# NRF52840-Beacon-V1-1.net
KiCad netlist of a schematic drawn in Altium Designer
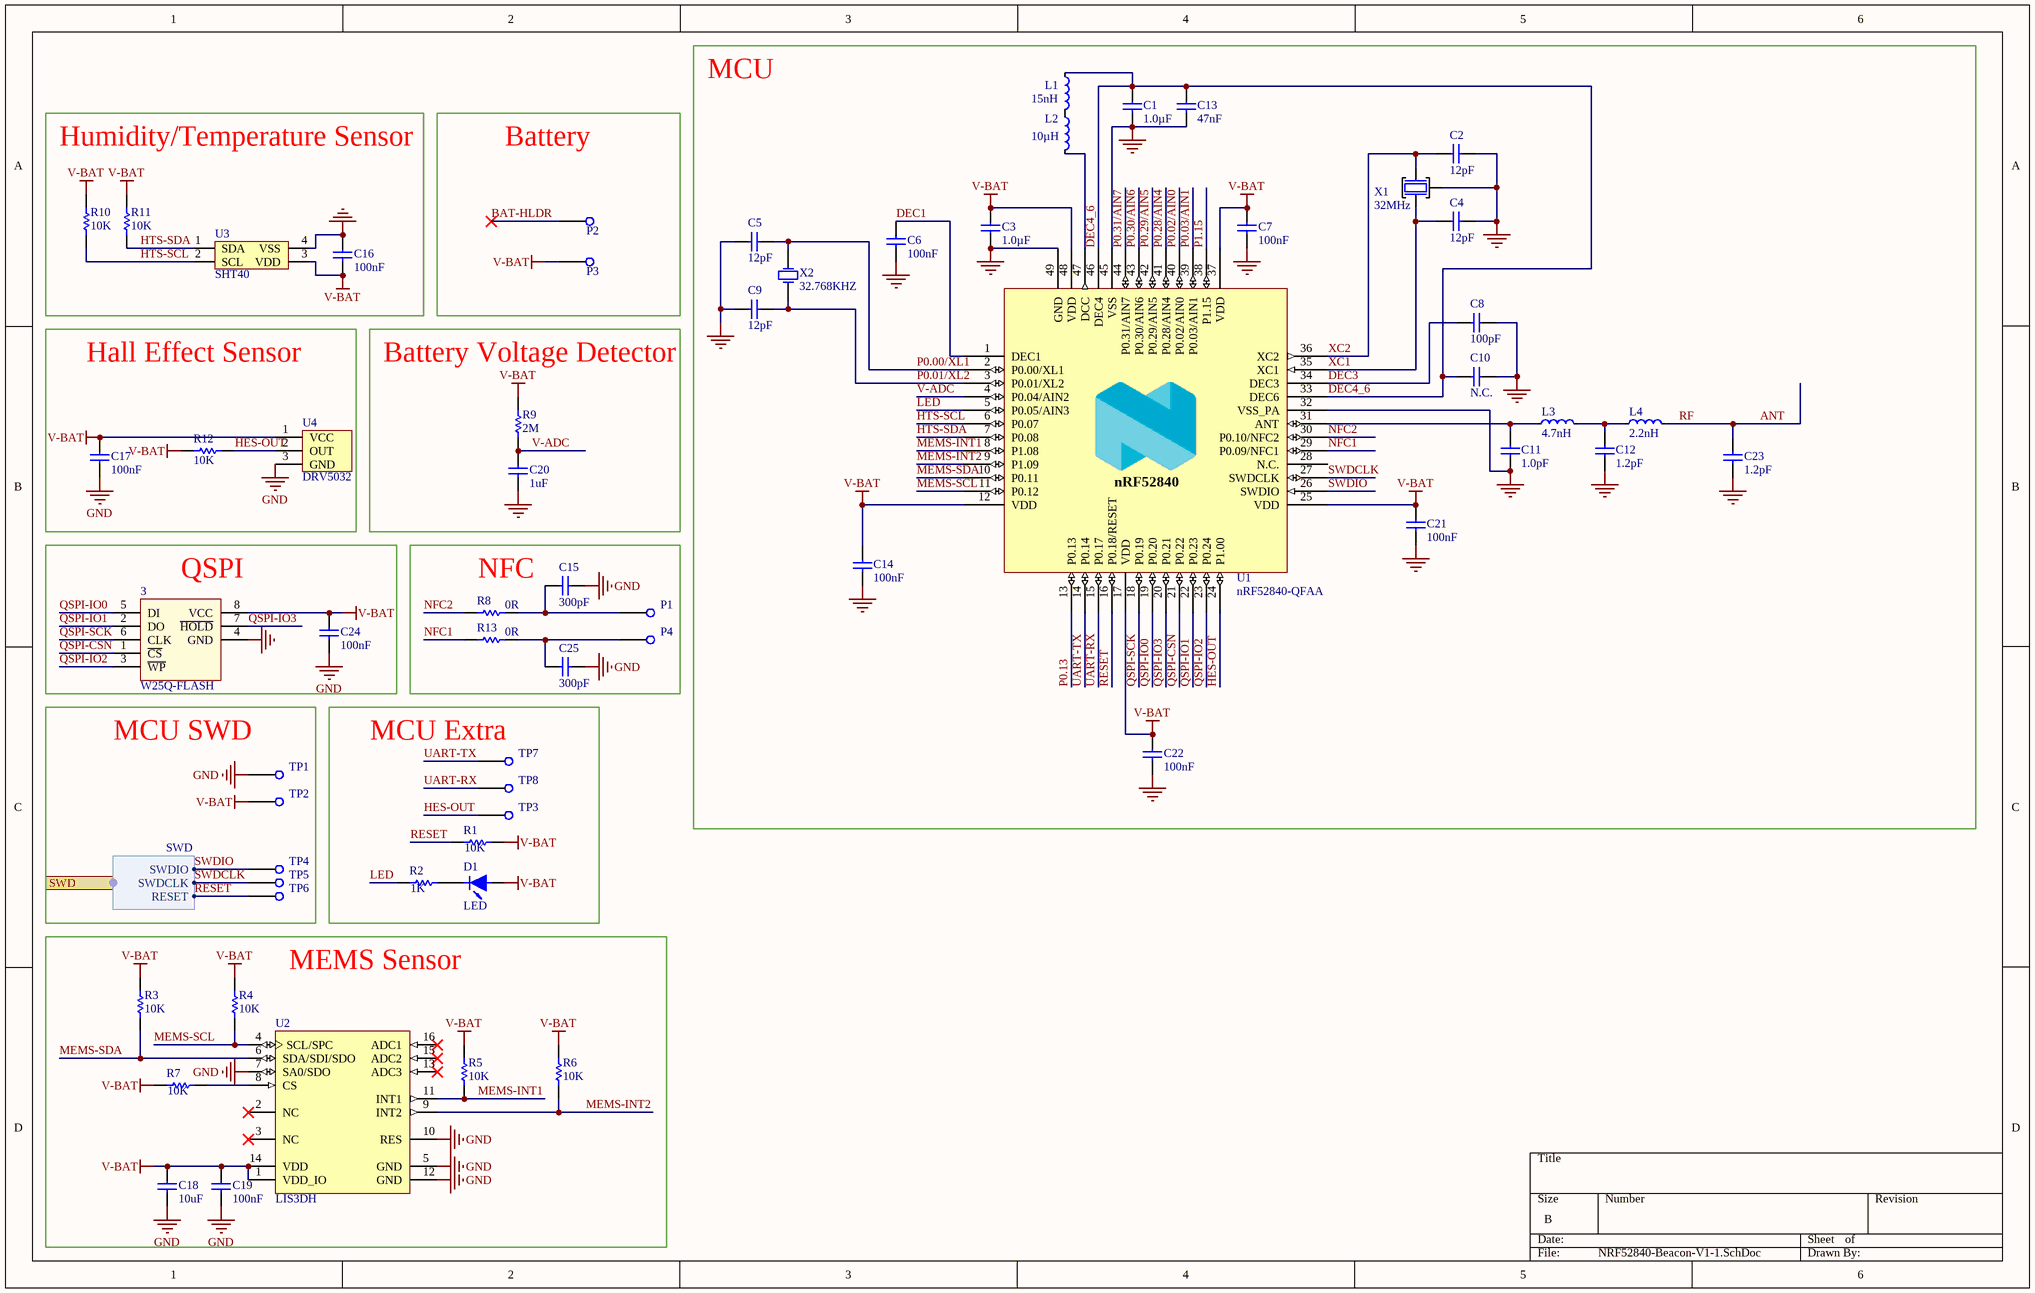
[diagram p0: NRF52840-Beacon-V1-1.SchDoc]

(export (version "E")
  (design (tool "Eeschema 10.0.6"))
  (components
    (comp (ref "3")
      (value "W25Q-FLASH")
      (footprint "SO8W_M")
      (libsource (lib "My Devices") (part "W25Q-FLASH"))
    )
    (comp (ref "C1")
      (value "1.0µF")
      (footprint "CAPC1608N")
      (description "Capacitor, X5R, ±10%")
      (fields (field (name "PART NUMBER") "C0402-1µ0"))
      (libsource (lib "AltiumLib") (part "CAP"))
    )
    (comp (ref "C2")
      (value "12pF")
      (footprint "CAPC1608N")
      (description "Capacitor, NP0, ±2%")
      (fields (field (name "PART NUMBER") "C0201-12p"))
      (libsource (lib "AltiumLib") (part "CAP"))
    )
    (comp (ref "C3")
      (value "1.0µF")
      (footprint "CAPC1608N")
      (description "Capacitor, X5R, ±10%")
      (fields (field (name "PART NUMBER") "C0402-1µ0"))
      (libsource (lib "AltiumLib") (part "CAP"))
    )
    (comp (ref "C4")
      (value "12pF")
      (footprint "CAPC1608N")
      (description "Capacitor, NP0, ±2%")
      (fields (field (name "PART NUMBER") "C0201-12p"))
      (libsource (lib "AltiumLib") (part "CAP"))
    )
    (comp (ref "C5")
      (value "12pF")
      (footprint "CAPC1608N")
      (description "Capacitor, NP0, ±2%")
      (fields (field (name "PART NUMBER") "C0201-12p"))
      (libsource (lib "AltiumLib") (part "CAP"))
    )
    (comp (ref "C6")
      (value "100nF")
      (footprint "CAPC1608N")
      (description "Capacitor, X5R, ±10%")
      (fields (field (name "PART NUMBER") "C0201-100n"))
      (libsource (lib "AltiumLib") (part "CAP"))
    )
    (comp (ref "C7")
      (value "100nF")
      (footprint "CAPC1608N")
      (description "Capacitor, X5R, ±10%")
      (fields (field (name "PART NUMBER") "C0201-100n"))
      (libsource (lib "AltiumLib") (part "CAP"))
    )
    (comp (ref "C8")
      (value "100pF")
      (footprint "CAPC1608N")
      (description "Capacitor, NP0, ±5%")
      (fields (field (name "PART NUMBER") "C0201-100p"))
      (libsource (lib "AltiumLib") (part "CAP"))
    )
    (comp (ref "C9")
      (value "12pF")
      (footprint "CAPC1608N")
      (description "Capacitor, NP0, ±2%")
      (fields (field (name "PART NUMBER") "C0201-12p"))
      (libsource (lib "AltiumLib") (part "CAP"))
    )
    (comp (ref "C10")
      (value "N.C.")
      (footprint "CAPC1608N")
      (description "Not mounted")
      (fields (field (name "PART NUMBER") "C0201-N.C."))
      (libsource (lib "AltiumLib") (part "CAP"))
    )
    (comp (ref "C11")
      (value "1.0pF")
      (footprint "CAPC1608N")
      (description "Capacitor, NP0, ±10%")
      (fields (field (name "PART NUMBER") "C0201-1.0p"))
      (libsource (lib "AltiumLib") (part "CAP"))
    )
    (comp (ref "C12")
      (value "1.2pF")
      (footprint "CAPC1608N")
      (description "Capacitor, NP0, ±10%")
      (fields (field (name "PART NUMBER") "C0201-1.2p"))
      (libsource (lib "AltiumLib") (part "CAP"))
    )
    (comp (ref "C13")
      (value "47nF")
      (footprint "CAPC1608N")
      (description "Capacitor, X5R, ±10%")
      (fields (field (name "PART NUMBER") "C0201-47n"))
      (libsource (lib "AltiumLib") (part "CAP"))
    )
    (comp (ref "C14")
      (value "100nF")
      (footprint "CAPC1608N")
      (description "Capacitor, X5R, ±10%")
      (fields (field (name "PART NUMBER") "C0201-100n"))
      (libsource (lib "AltiumLib") (part "CAP"))
    )
    (comp (ref "C15")
      (value "300pF")
      (footprint "CAPC1608N")
      (description "Capacitor, NP0, ±2%")
      (fields (field (name "PART NUMBER") "C0201-12p"))
      (libsource (lib "AltiumLib") (part "CAP"))
    )
    (comp (ref "C16")
      (value "100nF")
      (footprint "CAPC1608N")
      (description "Capacitor, NP0, ±2%")
      (fields (field (name "PART NUMBER") "C0201-12p"))
      (libsource (lib "AltiumLib") (part "CAP"))
    )
    (comp (ref "C17")
      (value "100nF")
      (footprint "CAPC1608N")
      (description "Capacitor, NP0, ±2%")
      (fields (field (name "PART NUMBER") "C0201-12p"))
      (libsource (lib "AltiumLib") (part "CAP"))
    )
    (comp (ref "C18")
      (value "10uF")
      (footprint "CAPC1608N")
      (description "Capacitor, NP0, ±2%")
      (fields (field (name "PART NUMBER") "C0201-12p"))
      (libsource (lib "AltiumLib") (part "CAP"))
    )
    (comp (ref "C19")
      (value "100nF")
      (footprint "CAPC1608N")
      (description "Capacitor, NP0, ±2%")
      (fields (field (name "PART NUMBER") "C0201-12p"))
      (libsource (lib "AltiumLib") (part "CAP"))
    )
    (comp (ref "C20")
      (value "1uF")
      (footprint "CAPC1608N")
      (description "Capacitor, NP0, ±2%")
      (fields (field (name "PART NUMBER") "C0201-12p"))
      (libsource (lib "AltiumLib") (part "CAP"))
    )
    (comp (ref "C21")
      (value "100nF")
      (footprint "CAPC1608N")
      (description "Capacitor, X5R, ±10%")
      (fields (field (name "PART NUMBER") "C0201-100n"))
      (libsource (lib "AltiumLib") (part "CAP"))
    )
    (comp (ref "C22")
      (value "100nF")
      (footprint "CAPC1608N")
      (description "Capacitor, X5R, ±10%")
      (fields (field (name "PART NUMBER") "C0201-100n"))
      (libsource (lib "AltiumLib") (part "CAP"))
    )
    (comp (ref "C23")
      (value "1.2pF")
      (footprint "CAPC1608N")
      (description "Capacitor, NP0, ±10%")
      (fields (field (name "PART NUMBER") "C0201-1.2p"))
      (libsource (lib "AltiumLib") (part "CAP"))
    )
    (comp (ref "C24")
      (value "100nF")
      (footprint "CAPC1608N")
      (description "Capacitor, NP0, ±2%")
      (fields (field (name "PART NUMBER") "C0201-12p"))
      (libsource (lib "AltiumLib") (part "CAP"))
    )
    (comp (ref "C25")
      (value "300pF")
      (footprint "CAPC1608N")
      (description "Capacitor, NP0, ±2%")
      (fields (field (name "PART NUMBER") "C0201-12p"))
      (libsource (lib "AltiumLib") (part "CAP"))
    )
    (comp (ref "D1")
      (value "LED")
      (footprint "LED_0603")
      (fields (field (name "PUBLISHER") "Altium Limited"))
      (libsource (lib "My Devices") (part "LED"))
    )
    (comp (ref "L1")
      (value "15nH")
      (footprint "INDC1608N")
      (description "High frequency chip inductor ±10%")
      (fields (field (name "PART NUMBER") "L0402-15n"))
      (libsource (lib "AltiumLib") (part "IND"))
    )
    (comp (ref "L2")
      (value "10µH")
      (footprint "INDC1608N")
      (description "Chip inductor, IDC,min = 50 mA, ±20%")
      (fields (field (name "PART NUMBER") "L0603-10µ-TDK"))
      (libsource (lib "AltiumLib") (part "IND"))
    )
    (comp (ref "L3")
      (value "4.7nH")
      (footprint "INDC1608N")
      (description "High frequency chip inductor ±5%")
      (fields (field (name "PART NUMBER") "L0201-4n7"))
      (libsource (lib "AltiumLib") (part "IND"))
    )
    (comp (ref "L4")
      (value "2.2nH")
      (footprint "INDC1608N")
      (description "High frequency chip inductor ±5%")
      (fields (field (name "PART NUMBER") "L0201-2n2"))
      (libsource (lib "AltiumLib") (part "IND"))
    )
    (comp (ref "P1") (value "PIN") (footprint "PIN") (libsource (lib "My Connectors") (part "PIN")))
    (comp (ref "P2") (value "PIN") (footprint "PIN") (libsource (lib "My Connectors") (part "PIN")))
    (comp (ref "P3") (value "PIN") (footprint "PIN") (libsource (lib "My Connectors") (part "PIN")))
    (comp (ref "P4") (value "PIN") (footprint "PIN") (libsource (lib "My Connectors") (part "PIN")))
    (comp (ref "R1") (value "10K") (footprint "RESC1608N") (libsource (lib "My Devices") (part "Resistor")))
    (comp (ref "R2") (value "1K") (footprint "RESC1608N") (libsource (lib "My Devices") (part "Resistor")))
    (comp (ref "R3") (value "10K") (footprint "RESC1608N") (libsource (lib "My Devices") (part "Resistor")))
    (comp (ref "R4") (value "10K") (footprint "RESC1608N") (libsource (lib "My Devices") (part "Resistor")))
    (comp (ref "R5") (value "10K") (footprint "RESC1608N") (libsource (lib "My Devices") (part "Resistor")))
    (comp (ref "R6") (value "10K") (footprint "RESC1608N") (libsource (lib "My Devices") (part "Resistor")))
    (comp (ref "R7") (value "10K") (footprint "RESC1608N") (libsource (lib "My Devices") (part "Resistor")))
    (comp (ref "R8") (value "0R") (footprint "RESC1608N") (libsource (lib "My Devices") (part "Resistor")))
    (comp (ref "R9") (value "2M") (footprint "RESC1608N") (libsource (lib "My Devices") (part "Resistor")))
    (comp (ref "R10") (value "10K") (footprint "RESC1608N") (libsource (lib "My Devices") (part "Resistor")))
    (comp (ref "R11") (value "10K") (footprint "RESC1608N") (libsource (lib "My Devices") (part "Resistor")))
    (comp (ref "R12") (value "10K") (footprint "RESC1608N") (libsource (lib "My Devices") (part "Resistor")))
    (comp (ref "R13") (value "0R") (footprint "RESC1608N") (libsource (lib "My Devices") (part "Resistor")))
    (comp (ref "TP1") (value "PIN") (footprint "PIN") (libsource (lib "My Connectors") (part "PIN")))
    (comp (ref "TP2") (value "PIN") (footprint "PIN") (libsource (lib "My Connectors") (part "PIN")))
    (comp (ref "TP3") (value "PIN") (footprint "PIN") (libsource (lib "My Connectors") (part "PIN")))
    (comp (ref "TP4") (value "PIN") (footprint "PIN") (libsource (lib "My Connectors") (part "PIN")))
    (comp (ref "TP5") (value "PIN") (footprint "PIN") (libsource (lib "My Connectors") (part "PIN")))
    (comp (ref "TP6") (value "PIN") (footprint "PIN") (libsource (lib "My Connectors") (part "PIN")))
    (comp (ref "TP7") (value "PIN") (footprint "PIN") (libsource (lib "My Connectors") (part "PIN")))
    (comp (ref "TP8") (value "PIN") (footprint "PIN") (libsource (lib "My Connectors") (part "PIN")))
    (comp (ref "U1")
      (value "nRF52840-QFAA")
      (footprint "QFN40P600X600X90-48N")
      (description "Multi-protocol Bluetooth Low Energy, IEEE 802.15.4, ANT and 2.4GHz proprietary system-on-chip")
      (libsource (lib "AltiumLib") (part "nRF52840_QFAA"))
    )
    (comp (ref "U2")
      (value "LIS3DH")
      (footprint "LGA-16")
      (fields (field (name "MANUFACTURER") "STMicroelectronics"))
      (libsource (lib "My Devices") (part "LIS3DH"))
    )
    (comp (ref "U3")
      (value "SHT40")
      (footprint "SHT40")
      (description "High-Accuracy, Ultra-Low-Power, 16-bit, Relative Humidity and Temperature Sensor")
      (libsource (lib "My Devices") (part "SHT40"))
    )
    (comp (ref "U4")
      (value "DRV5032")
      (footprint "SOT-23")
      (description "ultra-low-power digital-switch Hall effect sensor")
      (libsource (lib "My Devices") (part "Hall_Effect_Sensor_Switch"))
    )
    (comp (ref "X1")
      (value "32MHz")
      (footprint "CRYSTAL_2016_NT")
      (description "XTAL SMD 2016, 32MHz, Cl=8pF, Total Tol: ±30ppm")
      (fields (field (name "PART NUMBER") "XTAL_SMD2016_32MHz_8pF_General_NT"))
      (libsource (lib "AltiumLib") (part "XTAL_4-pin_NT"))
    )
    (comp (ref "X2")
      (value "32.768KHZ")
      (footprint "CRYSTAL_3215")
      (libsource (lib "My Devices") (part "Crystal_Oscillator_2PIN"))
    )
  )
  (nets
    (net (code "2") (name "/ANT") (class "Default")
      (node (ref "C23") (pin "1") (pinfunction "1_1") (pintype "passive"))
      (node (ref "L4") (pin "2") (pinfunction "2_2") (pintype "passive"))
    )
    (net (code "3") (name "/BAT-HLDR") (class "Default")
      (node (ref "P2") (pin "1") (pinfunction "PIN_1") (pintype "passive+no_connect"))
    )
    (net (code "4") (name "/DEC1") (class "Default")
      (node (ref "C6") (pin "1") (pinfunction "1_1") (pintype "passive"))
      (node (ref "U1") (pin "1") (pinfunction "DEC1_1") (pintype "power_in"))
    )
    (net (code "5") (name "/DEC3") (class "Default")
      (node (ref "C8") (pin "1") (pinfunction "1_1") (pintype "passive"))
      (node (ref "U1") (pin "34") (pinfunction "DEC3_34") (pintype "power_in"))
    )
    (net (code "6") (name "/DEC4_6") (class "Default")
      (node (ref "C1") (pin "2") (pinfunction "2_2") (pintype "passive"))
      (node (ref "C10") (pin "2") (pinfunction "2_2") (pintype "passive"))
      (node (ref "C13") (pin "1") (pinfunction "1_1") (pintype "passive"))
      (node (ref "L1") (pin "1") (pinfunction "1_1") (pintype "passive"))
      (node (ref "U1") (pin "33") (pinfunction "DEC6_33") (pintype "power_in"))
      (node (ref "U1") (pin "46") (pinfunction "DEC4_46") (pintype "power_in"))
    )
    (net (code "7") (name "/HES-OUT") (class "Default")
      (node (ref "R12") (pin "2") (pinfunction "2_2") (pintype "passive"))
      (node (ref "TP3") (pin "1") (pinfunction "PIN_1") (pintype "passive"))
      (node (ref "U1") (pin "24") (pinfunction "P1.00_24") (pintype "bidirectional"))
      (node (ref "U4") (pin "2") (pinfunction "OUT_2") (pintype "passive"))
    )
    (net (code "8") (name "/HTS-SCL") (class "Default")
      (node (ref "R10") (pin "2") (pinfunction "2_2") (pintype "passive"))
      (node (ref "U1") (pin "6") (pinfunction "P0.07_6") (pintype "bidirectional"))
      (node (ref "U3") (pin "2") (pinfunction "SCL_2") (pintype "passive"))
    )
    (net (code "9") (name "/HTS-SDA") (class "Default")
      (node (ref "R11") (pin "2") (pinfunction "2_2") (pintype "passive"))
      (node (ref "U1") (pin "7") (pinfunction "P0.08_7") (pintype "bidirectional"))
      (node (ref "U3") (pin "1") (pinfunction "SDA_1") (pintype "passive"))
    )
    (net (code "10") (name "/LED") (class "Default")
      (node (ref "R2") (pin "1") (pinfunction "1_1") (pintype "passive"))
      (node (ref "U1") (pin "5") (pinfunction "P0.05/AIN3_5") (pintype "bidirectional"))
    )
    (net (code "11") (name "/MEMS-INT1") (class "Default")
      (node (ref "R5") (pin "2") (pinfunction "2_2") (pintype "passive"))
      (node (ref "U1") (pin "8") (pinfunction "P1.08_8") (pintype "bidirectional"))
      (node (ref "U2") (pin "11") (pinfunction "INT1_11") (pintype "output"))
    )
    (net (code "12") (name "/MEMS-INT2") (class "Default")
      (node (ref "R6") (pin "2") (pinfunction "2_2") (pintype "passive"))
      (node (ref "U1") (pin "9") (pinfunction "P1.09_9") (pintype "bidirectional"))
      (node (ref "U2") (pin "9") (pinfunction "INT2_9") (pintype "output"))
    )
    (net (code "13") (name "/MEMS-SCL") (class "Default")
      (node (ref "R4") (pin "2") (pinfunction "2_2") (pintype "passive"))
      (node (ref "U1") (pin "11") (pinfunction "P0.12_11") (pintype "bidirectional"))
      (node (ref "U2") (pin "4") (pinfunction "SCL/SPC_4") (pintype "bidirectional"))
    )
    (net (code "14") (name "/MEMS-SDA") (class "Default")
      (node (ref "R3") (pin "2") (pinfunction "2_2") (pintype "passive"))
      (node (ref "U1") (pin "10") (pinfunction "P0.11_10") (pintype "bidirectional"))
      (node (ref "U2") (pin "6") (pinfunction "SDA/SDI/SDO_6") (pintype "bidirectional"))
    )
    (net (code "15") (name "/NFC1") (class "Default")
      (node (ref "R13") (pin "2") (pinfunction "2_2") (pintype "passive"))
      (node (ref "U1") (pin "29") (pinfunction "P0.09/NFC1_29") (pintype "bidirectional"))
    )
    (net (code "16") (name "/NFC2") (class "Default")
      (node (ref "R8") (pin "2") (pinfunction "2_2") (pintype "passive"))
      (node (ref "U1") (pin "30") (pinfunction "P0.10/NFC2_30") (pintype "bidirectional"))
    )
    (net (code "17") (name "/P0.00{slash}XL1") (class "Default")
      (node (ref "C5") (pin "1") (pinfunction "1_1") (pintype "passive"))
      (node (ref "U1") (pin "2") (pinfunction "P0.00/XL1_2") (pintype "bidirectional"))
      (node (ref "X2") (pin "2") (pinfunction "OSC2_2") (pintype "passive"))
    )
    (net (code "18") (name "/P0.01{slash}XL2") (class "Default")
      (node (ref "C9") (pin "1") (pinfunction "1_1") (pintype "passive"))
      (node (ref "U1") (pin "3") (pinfunction "P0.01/XL2_3") (pintype "bidirectional"))
      (node (ref "X2") (pin "1") (pinfunction "OSC1_1") (pintype "passive"))
    )
    (net (code "19") (name "/P0.02{slash}AIN0") (class "Default")
      (node (ref "U1") (pin "40") (pinfunction "P0.02/AIN0_40") (pintype "bidirectional"))
    )
    (net (code "20") (name "/P0.03{slash}AIN1") (class "Default")
      (node (ref "U1") (pin "39") (pinfunction "P0.03/AIN1_39") (pintype "bidirectional"))
    )
    (net (code "21") (name "/P0.13") (class "Default")
      (node (ref "U1") (pin "13") (pinfunction "P0.13_13") (pintype "bidirectional"))
    )
    (net (code "22") (name "/P0.28{slash}AIN4") (class "Default")
      (node (ref "U1") (pin "41") (pinfunction "P0.28/AIN4_41") (pintype "bidirectional"))
    )
    (net (code "23") (name "/P0.29{slash}AIN5") (class "Default")
      (node (ref "U1") (pin "42") (pinfunction "P0.29/AIN5_42") (pintype "bidirectional"))
    )
    (net (code "24") (name "/P0.30{slash}AIN6") (class "Default")
      (node (ref "U1") (pin "43") (pinfunction "P0.30/AIN6_43") (pintype "bidirectional"))
    )
    (net (code "25") (name "/P0.31{slash}AIN7") (class "Default")
      (node (ref "U1") (pin "44") (pinfunction "P0.31/AIN7_44") (pintype "bidirectional"))
    )
    (net (code "26") (name "/P1.15") (class "Default")
      (node (ref "U1") (pin "38") (pinfunction "P1.15_38") (pintype "bidirectional"))
    )
    (net (code "27") (name "/QSPI-CSN") (class "Default")
      (node (ref "3") (pin "1") (pinfunction "~{CS}_1") (pintype "passive"))
      (node (ref "U1") (pin "21") (pinfunction "P0.22_21") (pintype "bidirectional"))
    )
    (net (code "28") (name "/QSPI-IO0") (class "Default")
      (node (ref "3") (pin "5") (pinfunction "DI_5") (pintype "passive"))
      (node (ref "U1") (pin "19") (pinfunction "P0.20_19") (pintype "bidirectional"))
    )
    (net (code "29") (name "/QSPI-IO1") (class "Default")
      (node (ref "3") (pin "2") (pinfunction "DO_2") (pintype "passive"))
      (node (ref "U1") (pin "22") (pinfunction "P0.23_22") (pintype "bidirectional"))
    )
    (net (code "30") (name "/QSPI-IO2") (class "Default")
      (node (ref "3") (pin "3") (pinfunction "~{WP}_3") (pintype "passive"))
      (node (ref "U1") (pin "23") (pinfunction "P0.24_23") (pintype "bidirectional"))
    )
    (net (code "31") (name "/QSPI-IO3") (class "Default")
      (node (ref "3") (pin "7") (pinfunction "~{HOLD}_7") (pintype "passive"))
      (node (ref "U1") (pin "20") (pinfunction "P0.21_20") (pintype "bidirectional"))
    )
    (net (code "32") (name "/QSPI-SCK") (class "Default")
      (node (ref "3") (pin "6") (pinfunction "CLK_6") (pintype "passive"))
      (node (ref "U1") (pin "18") (pinfunction "P0.19_18") (pintype "bidirectional"))
    )
    (net (code "33") (name "/RESET") (class "Default")
      (node (ref "R1") (pin "1") (pinfunction "1_1") (pintype "passive"))
      (node (ref "TP6") (pin "1") (pinfunction "PIN_1") (pintype "passive"))
      (node (ref "U1") (pin "16") (pinfunction "P0.18/RESET_16") (pintype "bidirectional"))
    )
    (net (code "34") (name "/SWDCLK") (class "Default")
      (node (ref "TP5") (pin "1") (pinfunction "PIN_1") (pintype "passive"))
      (node (ref "U1") (pin "27") (pinfunction "SWDCLK_27") (pintype "bidirectional"))
    )
    (net (code "35") (name "/SWDIO") (class "Default")
      (node (ref "TP4") (pin "1") (pinfunction "PIN_1") (pintype "passive"))
      (node (ref "U1") (pin "26") (pinfunction "SWDIO_26") (pintype "input"))
    )
    (net (code "36") (name "/UART-RX") (class "Default")
      (node (ref "TP8") (pin "1") (pinfunction "PIN_1") (pintype "passive"))
      (node (ref "U1") (pin "15") (pinfunction "P0.17_15") (pintype "bidirectional"))
    )
    (net (code "37") (name "/UART-TX") (class "Default")
      (node (ref "TP7") (pin "1") (pinfunction "PIN_1") (pintype "passive"))
      (node (ref "U1") (pin "14") (pinfunction "P0.14_14") (pintype "bidirectional"))
    )
    (net (code "38") (name "/V-ADC") (class "Default")
      (node (ref "C20") (pin "1") (pinfunction "1_1") (pintype "passive"))
      (node (ref "R9") (pin "1") (pinfunction "1_1") (pintype "passive"))
      (node (ref "U1") (pin "4") (pinfunction "P0.04/AIN2_4") (pintype "bidirectional"))
    )
    (net (code "39") (name "/XC1") (class "Default")
      (node (ref "C4") (pin "1") (pinfunction "1_1") (pintype "passive"))
      (node (ref "U1") (pin "35") (pinfunction "XC1_35") (pintype "input"))
      (node (ref "X1") (pin "1") (pinfunction "IN_1") (pintype "passive"))
    )
    (net (code "40") (name "/XC2") (class "Default")
      (node (ref "C2") (pin "1") (pinfunction "1_1") (pintype "passive"))
      (node (ref "U1") (pin "36") (pinfunction "XC2_36") (pintype "output"))
      (node (ref "X1") (pin "3") (pinfunction "OUT_3") (pintype "passive"))
    )
    (net (code "42") (name "GND") (class "Default")
      (node (ref "3") (pin "4") (pinfunction "GND_4") (pintype "passive"))
      (node (ref "C1") (pin "1") (pinfunction "1_1") (pintype "passive"))
      (node (ref "C10") (pin "1") (pinfunction "1_1") (pintype "passive"))
      (node (ref "C11") (pin "1") (pinfunction "1_1") (pintype "passive"))
      (node (ref "C12") (pin "1") (pinfunction "1_1") (pintype "passive"))
      (node (ref "C13") (pin "2") (pinfunction "2_2") (pintype "passive"))
      (node (ref "C14") (pin "2") (pinfunction "2_2") (pintype "passive"))
      (node (ref "C15") (pin "2") (pinfunction "2_2") (pintype "passive"))
      (node (ref "C16") (pin "1") (pinfunction "1_1") (pintype "passive"))
      (node (ref "C17") (pin "2") (pinfunction "2_2") (pintype "passive"))
      (node (ref "C18") (pin "2") (pinfunction "2_2") (pintype "passive"))
      (node (ref "C19") (pin "2") (pinfunction "2_2") (pintype "passive"))
      (node (ref "C2") (pin "2") (pinfunction "2_2") (pintype "passive"))
      (node (ref "C20") (pin "2") (pinfunction "2_2") (pintype "passive"))
      (node (ref "C21") (pin "2") (pinfunction "2_2") (pintype "passive"))
      (node (ref "C22") (pin "2") (pinfunction "2_2") (pintype "passive"))
      (node (ref "C23") (pin "2") (pinfunction "2_2") (pintype "passive"))
      (node (ref "C24") (pin "2") (pinfunction "2_2") (pintype "passive"))
      (node (ref "C25") (pin "2") (pinfunction "2_2") (pintype "passive"))
      (node (ref "C3") (pin "2") (pinfunction "2_2") (pintype "passive"))
      (node (ref "C4") (pin "2") (pinfunction "2_2") (pintype "passive"))
      (node (ref "C5") (pin "2") (pinfunction "2_2") (pintype "passive"))
      (node (ref "C6") (pin "2") (pinfunction "2_2") (pintype "passive"))
      (node (ref "C7") (pin "2") (pinfunction "2_2") (pintype "passive"))
      (node (ref "C8") (pin "2") (pinfunction "2_2") (pintype "passive"))
      (node (ref "C9") (pin "2") (pinfunction "2_2") (pintype "passive"))
      (node (ref "TP1") (pin "1") (pinfunction "PIN_1") (pintype "passive"))
      (node (ref "U1") (pin "32") (pinfunction "VSS_PA_32") (pintype "power_in"))
      (node (ref "U1") (pin "45") (pinfunction "VSS_45") (pintype "power_in"))
      (node (ref "U1") (pin "49") (pinfunction "GND_49") (pintype "power_in"))
      (node (ref "U2") (pin "10") (pinfunction "RES_10") (pintype "power_in"))
      (node (ref "U2") (pin "12") (pinfunction "GND_12") (pintype "power_in"))
      (node (ref "U2") (pin "5") (pinfunction "GND_5") (pintype "power_in"))
      (node (ref "U2") (pin "7") (pinfunction "SA0/SDO_7") (pintype "bidirectional"))
      (node (ref "U3") (pin "4") (pinfunction "VSS_4") (pintype "passive"))
      (node (ref "U4") (pin "3") (pinfunction "GND_3") (pintype "passive"))
      (node (ref "X1") (pin "2") (pinfunction "GND_2") (pintype "passive"))
    )
    (net (code "43") (name "Net-(C12-Pad2)") (class "Default")
      (node (ref "C12") (pin "2") (pinfunction "2_2") (pintype "passive"))
      (node (ref "L3") (pin "2") (pinfunction "2_2") (pintype "passive"))
      (node (ref "L4") (pin "1") (pinfunction "1_1") (pintype "passive"))
    )
    (net (code "44") (name "Net-(D1-K)") (class "Default")
      (node (ref "D1") (pin "2") (pinfunction "K_2") (pintype "passive"))
      (node (ref "R2") (pin "2") (pinfunction "2_2") (pintype "passive"))
    )
    (net (code "45") (name "Net-(L1-Pad2)") (class "Default")
      (node (ref "L1") (pin "2") (pinfunction "2_2") (pintype "passive"))
      (node (ref "L2") (pin "1") (pinfunction "1_1") (pintype "passive"))
    )
    (net (code "46") (name "Net-(P1-PIN)") (class "Default")
      (node (ref "C15") (pin "1") (pinfunction "1_1") (pintype "passive"))
      (node (ref "P1") (pin "1") (pinfunction "PIN_1") (pintype "passive"))
      (node (ref "R8") (pin "1") (pinfunction "1_1") (pintype "passive"))
    )
    (net (code "47") (name "Net-(P4-PIN)") (class "Default")
      (node (ref "C25") (pin "1") (pinfunction "1_1") (pintype "passive"))
      (node (ref "P4") (pin "1") (pinfunction "PIN_1") (pintype "passive"))
      (node (ref "R13") (pin "1") (pinfunction "1_1") (pintype "passive"))
    )
    (net (code "48") (name "Net-(U1-ANT)") (class "Default")
      (node (ref "C11") (pin "2") (pinfunction "2_2") (pintype "passive"))
      (node (ref "L3") (pin "1") (pinfunction "1_1") (pintype "passive"))
      (node (ref "U1") (pin "31") (pinfunction "ANT_31") (pintype "bidirectional"))
    )
    (net (code "49") (name "Net-(U1-DCC)") (class "Default")
      (node (ref "L2") (pin "2") (pinfunction "2_2") (pintype "passive"))
      (node (ref "U1") (pin "47") (pinfunction "DCC_47") (pintype "output"))
    )
    (net (code "50") (name "Net-(U2-CS)") (class "Default")
      (node (ref "R7") (pin "2") (pinfunction "2_2") (pintype "passive"))
      (node (ref "U2") (pin "8") (pinfunction "CS_8") (pintype "input"))
    )
    (net (code "51") (name "V-BAT") (class "Default")
      (node (ref "3") (pin "8") (pinfunction "VCC_8") (pintype "passive"))
      (node (ref "C14") (pin "1") (pinfunction "1_1") (pintype "passive"))
      (node (ref "C16") (pin "2") (pinfunction "2_2") (pintype "passive"))
      (node (ref "C17") (pin "1") (pinfunction "1_1") (pintype "passive"))
      (node (ref "C18") (pin "1") (pinfunction "1_1") (pintype "passive"))
      (node (ref "C19") (pin "1") (pinfunction "1_1") (pintype "passive"))
      (node (ref "C21") (pin "1") (pinfunction "1_1") (pintype "passive"))
      (node (ref "C22") (pin "1") (pinfunction "1_1") (pintype "passive"))
      (node (ref "C24") (pin "1") (pinfunction "1_1") (pintype "passive"))
      (node (ref "C3") (pin "1") (pinfunction "1_1") (pintype "passive"))
      (node (ref "C7") (pin "1") (pinfunction "1_1") (pintype "passive"))
      (node (ref "D1") (pin "1") (pinfunction "A_1") (pintype "passive"))
      (node (ref "P3") (pin "1") (pinfunction "PIN_1") (pintype "passive"))
      (node (ref "R1") (pin "2") (pinfunction "2_2") (pintype "passive"))
      (node (ref "R10") (pin "1") (pinfunction "1_1") (pintype "passive"))
      (node (ref "R11") (pin "1") (pinfunction "1_1") (pintype "passive"))
      (node (ref "R12") (pin "1") (pinfunction "1_1") (pintype "passive"))
      (node (ref "R3") (pin "1") (pinfunction "1_1") (pintype "passive"))
      (node (ref "R4") (pin "1") (pinfunction "1_1") (pintype "passive"))
      (node (ref "R5") (pin "1") (pinfunction "1_1") (pintype "passive"))
      (node (ref "R6") (pin "1") (pinfunction "1_1") (pintype "passive"))
      (node (ref "R7") (pin "1") (pinfunction "1_1") (pintype "passive"))
      (node (ref "R9") (pin "2") (pinfunction "2_2") (pintype "passive"))
      (node (ref "TP2") (pin "1") (pinfunction "PIN_1") (pintype "passive"))
      (node (ref "U1") (pin "12") (pinfunction "VDD_12") (pintype "power_in"))
      (node (ref "U1") (pin "17") (pinfunction "VDD_17") (pintype "power_in"))
      (node (ref "U1") (pin "25") (pinfunction "VDD_25") (pintype "power_in"))
      (node (ref "U1") (pin "37") (pinfunction "VDD_37") (pintype "power_in"))
      (node (ref "U1") (pin "48") (pinfunction "VDD_48") (pintype "power_in"))
      (node (ref "U2") (pin "1") (pinfunction "VDD_IO_1") (pintype "power_in"))
      (node (ref "U2") (pin "14") (pinfunction "VDD_14") (pintype "power_in"))
      (node (ref "U3") (pin "3") (pinfunction "VDD_3") (pintype "passive"))
      (node (ref "U4") (pin "1") (pinfunction "VCC_1") (pintype "passive"))
    )
    (net (code "52") (name "unconnected-(U1-N.C.-Pad28)") (class "Default")
      (node (ref "U1") (pin "28") (pinfunction "N.C._28") (pintype "passive"))
    )
    (net (code "53") (name "unconnected-(U2-ADC1-Pad16)") (class "Default")
      (node (ref "U2") (pin "16") (pinfunction "ADC1_16") (pintype "input+no_connect"))
    )
    (net (code "54") (name "unconnected-(U2-ADC2-Pad15)") (class "Default")
      (node (ref "U2") (pin "15") (pinfunction "ADC2_15") (pintype "input+no_connect"))
    )
    (net (code "55") (name "unconnected-(U2-ADC3-Pad13)") (class "Default")
      (node (ref "U2") (pin "13") (pinfunction "ADC3_13") (pintype "input+no_connect"))
    )
    (net (code "56") (name "unconnected-(U2-NC-Pad2)") (class "Default")
      (node (ref "U2") (pin "2") (pinfunction "NC_2") (pintype "passive+no_connect"))
    )
    (net (code "57") (name "unconnected-(U2-NC-Pad3)") (class "Default")
      (node (ref "U2") (pin "3") (pinfunction "NC_3") (pintype "passive+no_connect"))
    )
  )
)
